# FPGA_03.net
KiCad netlist of a schematic drawn in Altium Designer
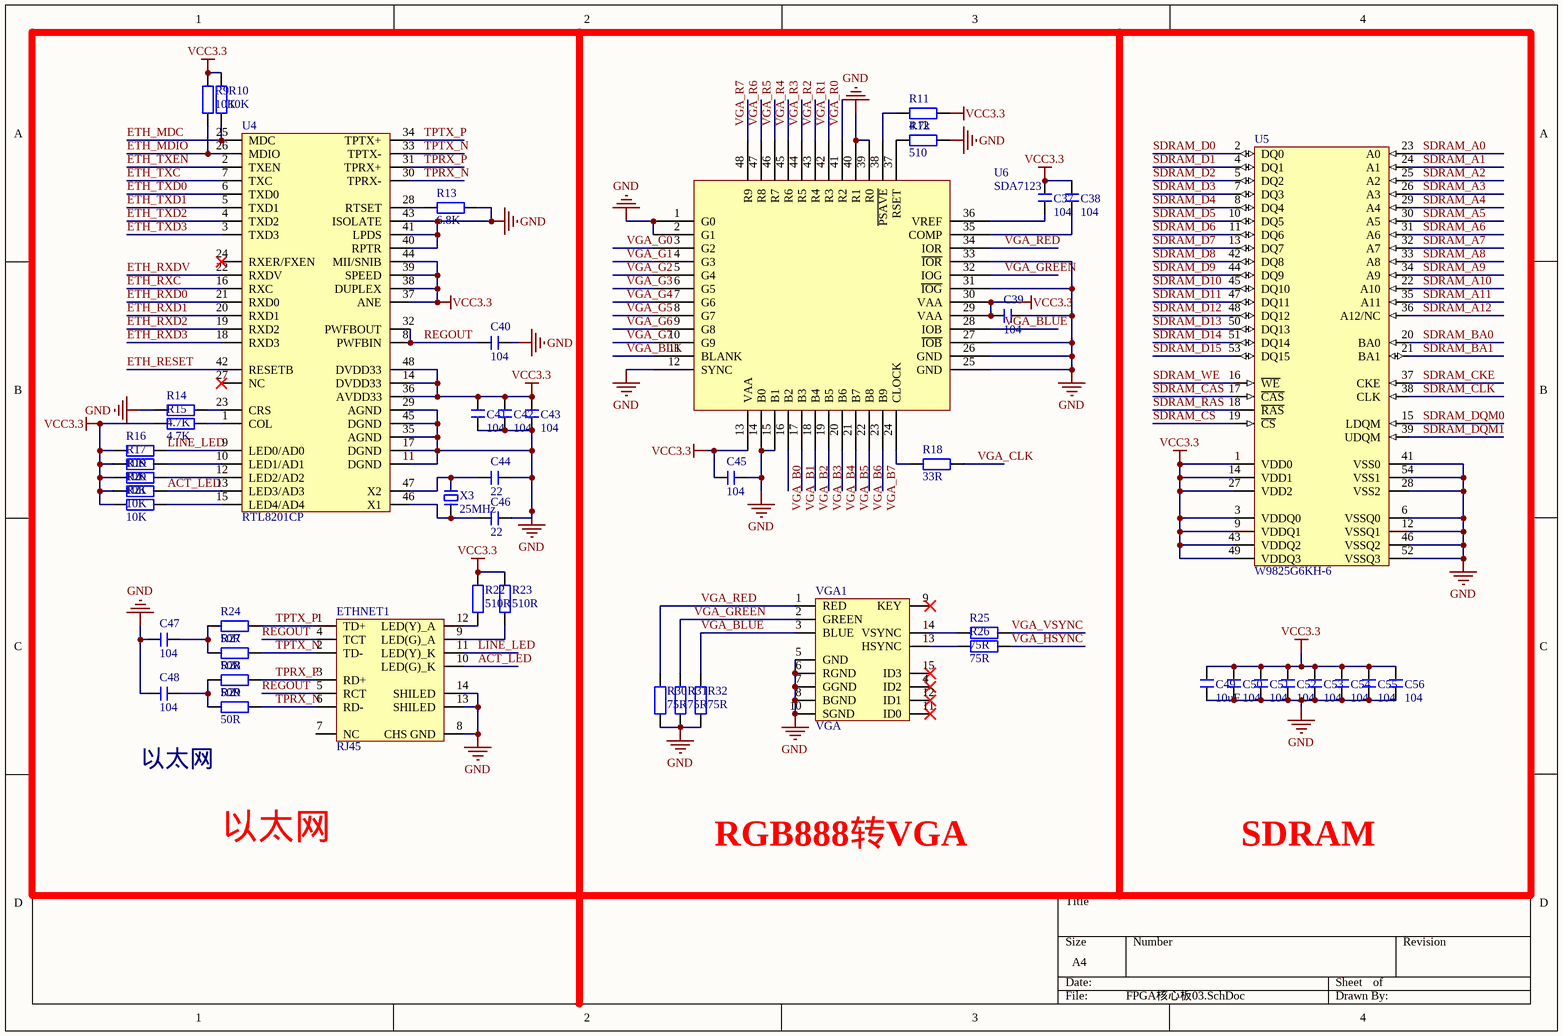
[diagram p0: FPGA核心板03.SchDoc]

(export (version "E")
  (design (tool "Eeschema 10.0.6"))
  (components
    (comp (ref "C37")
      (value "104")
      (footprint "C 0603_L")
      (description "贴片电容")
      (libsource (lib "0.1 - 电阻-电容-电感") (part "C"))
    )
    (comp (ref "C38")
      (value "104")
      (footprint "C 0603_L")
      (description "贴片电容")
      (libsource (lib "0.1 - 电阻-电容-电感") (part "C"))
    )
    (comp (ref "C39")
      (value "104")
      (footprint "C 0603_L")
      (description "贴片电容")
      (libsource (lib "0.1 - 电阻-电容-电感") (part "C"))
    )
    (comp (ref "C40")
      (value "104")
      (footprint "C 0603_L")
      (description "贴片电容")
      (libsource (lib "0.1 - 电阻-电容-电感") (part "C"))
    )
    (comp (ref "C41")
      (value "104")
      (footprint "C 0603_L")
      (description "贴片电容")
      (libsource (lib "0.1 - 电阻-电容-电感") (part "C"))
    )
    (comp (ref "C42")
      (value "104")
      (footprint "C 0603_L")
      (description "贴片电容")
      (libsource (lib "0.1 - 电阻-电容-电感") (part "C"))
    )
    (comp (ref "C43")
      (value "104")
      (footprint "C 0603_L")
      (description "贴片电容")
      (libsource (lib "0.1 - 电阻-电容-电感") (part "C"))
    )
    (comp (ref "C44")
      (value "22")
      (footprint "C 0603_L")
      (description "贴片电容")
      (libsource (lib "0.1 - 电阻-电容-电感") (part "C"))
    )
    (comp (ref "C45")
      (value "104")
      (footprint "C 0603_L")
      (description "贴片电容")
      (libsource (lib "0.1 - 电阻-电容-电感") (part "C"))
    )
    (comp (ref "C46")
      (value "22")
      (footprint "C 0603_L")
      (description "贴片电容")
      (libsource (lib "0.1 - 电阻-电容-电感") (part "C"))
    )
    (comp (ref "C47")
      (value "104")
      (footprint "C 0603_L")
      (description "贴片电容")
      (libsource (lib "0.1 - 电阻-电容-电感") (part "C"))
    )
    (comp (ref "C48")
      (value "104")
      (footprint "C 0603_L")
      (description "贴片电容")
      (libsource (lib "0.1 - 电阻-电容-电感") (part "C"))
    )
    (comp (ref "C49")
      (value "10uF")
      (footprint "C 0603_L")
      (description "贴片电容")
      (libsource (lib "0.1 - 电阻-电容-电感") (part "C"))
    )
    (comp (ref "C50")
      (value "104")
      (footprint "C 0603_L")
      (description "贴片电容")
      (libsource (lib "0.1 - 电阻-电容-电感") (part "C"))
    )
    (comp (ref "C51")
      (value "104")
      (footprint "C 0603_L")
      (description "贴片电容")
      (libsource (lib "0.1 - 电阻-电容-电感") (part "C"))
    )
    (comp (ref "C52")
      (value "104")
      (footprint "C 0603_L")
      (description "贴片电容")
      (libsource (lib "0.1 - 电阻-电容-电感") (part "C"))
    )
    (comp (ref "C53")
      (value "104")
      (footprint "C 0603_L")
      (description "贴片电容")
      (libsource (lib "0.1 - 电阻-电容-电感") (part "C"))
    )
    (comp (ref "C54")
      (value "104")
      (footprint "C 0603_L")
      (description "贴片电容")
      (libsource (lib "0.1 - 电阻-电容-电感") (part "C"))
    )
    (comp (ref "C55")
      (value "104")
      (footprint "C 0603_L")
      (description "贴片电容")
      (libsource (lib "0.1 - 电阻-电容-电感") (part "C"))
    )
    (comp (ref "C56")
      (value "104")
      (footprint "C 0603_L")
      (description "贴片电容")
      (libsource (lib "0.1 - 电阻-电容-电感") (part "C"))
    )
    (comp (ref "ETHNET1") (value "RJ45") (footprint "RJ-45A12") (libsource (lib "PIONEER") (part "HR911105")))
    (comp (ref "R9")
      (value "10K")
      (footprint "R 0603_L")
      (description "贴片电阻")
      (fields (field (name "版权归属") "来自淘宝 ID：黄晶宝石"))
      (libsource (lib "0.1 - 电阻-电容-电感") (part "R"))
    )
    (comp (ref "R10")
      (value "10K")
      (footprint "R 0603_L")
      (description "贴片电阻")
      (fields (field (name "版权归属") "来自淘宝 ID：黄晶宝石"))
      (libsource (lib "0.1 - 电阻-电容-电感") (part "R"))
    )
    (comp (ref "R11")
      (value "4.7k")
      (footprint "R 0603_L")
      (description "贴片电阻")
      (fields (field (name "版权归属") "来自淘宝 ID：黄晶宝石"))
      (libsource (lib "0.1 - 电阻-电容-电感") (part "R"))
    )
    (comp (ref "R12")
      (value "510")
      (footprint "R 0603_L")
      (description "贴片电阻")
      (fields (field (name "版权归属") "来自淘宝 ID：黄晶宝石"))
      (libsource (lib "0.1 - 电阻-电容-电感") (part "R"))
    )
    (comp (ref "R13")
      (value "6.8K")
      (footprint "R 0603_L")
      (description "贴片电阻")
      (fields (field (name "版权归属") "来自淘宝 ID：黄晶宝石"))
      (libsource (lib "0.1 - 电阻-电容-电感") (part "R"))
    )
    (comp (ref "R14")
      (value "4.7K")
      (footprint "R 0603_L")
      (description "贴片电阻")
      (fields (field (name "版权归属") "来自淘宝 ID：黄晶宝石"))
      (libsource (lib "0.1 - 电阻-电容-电感") (part "R"))
    )
    (comp (ref "R15")
      (value "4.7K")
      (footprint "R 0603_L")
      (description "贴片电阻")
      (fields (field (name "版权归属") "来自淘宝 ID：黄晶宝石"))
      (libsource (lib "0.1 - 电阻-电容-电感") (part "R"))
    )
    (comp (ref "R16")
      (value "10K")
      (footprint "R 0603_L")
      (description "贴片电阻")
      (fields (field (name "版权归属") "来自淘宝 ID：黄晶宝石"))
      (libsource (lib "0.1 - 电阻-电容-电感") (part "R"))
    )
    (comp (ref "R17")
      (value "10K")
      (footprint "R 0603_L")
      (description "贴片电阻")
      (fields (field (name "版权归属") "来自淘宝 ID：黄晶宝石"))
      (libsource (lib "0.1 - 电阻-电容-电感") (part "R"))
    )
    (comp (ref "R18")
      (value "33R")
      (footprint "R 0603_L")
      (description "贴片电阻")
      (fields (field (name "版权归属") "来自淘宝 ID：黄晶宝石"))
      (libsource (lib "0.1 - 电阻-电容-电感") (part "R"))
    )
    (comp (ref "R19")
      (value "10K")
      (footprint "R 0603_L")
      (description "贴片电阻")
      (fields (field (name "版权归属") "来自淘宝 ID：黄晶宝石"))
      (libsource (lib "0.1 - 电阻-电容-电感") (part "R"))
    )
    (comp (ref "R20")
      (value "10K")
      (footprint "R 0603_L")
      (description "贴片电阻")
      (fields (field (name "版权归属") "来自淘宝 ID：黄晶宝石"))
      (libsource (lib "0.1 - 电阻-电容-电感") (part "R"))
    )
    (comp (ref "R21")
      (value "10K")
      (footprint "R 0603_L")
      (description "贴片电阻")
      (fields (field (name "版权归属") "来自淘宝 ID：黄晶宝石"))
      (libsource (lib "0.1 - 电阻-电容-电感") (part "R"))
    )
    (comp (ref "R22")
      (value "510R")
      (footprint "R 0603_L")
      (description "贴片电阻")
      (fields (field (name "版权归属") "来自淘宝 ID：黄晶宝石"))
      (libsource (lib "0.1 - 电阻-电容-电感") (part "R"))
    )
    (comp (ref "R23")
      (value "510R")
      (footprint "R 0603_L")
      (description "贴片电阻")
      (fields (field (name "版权归属") "来自淘宝 ID：黄晶宝石"))
      (libsource (lib "0.1 - 电阻-电容-电感") (part "R"))
    )
    (comp (ref "R24")
      (value "50R")
      (footprint "R 0603_L")
      (description "贴片电阻")
      (fields (field (name "版权归属") "来自淘宝 ID：黄晶宝石"))
      (libsource (lib "0.1 - 电阻-电容-电感") (part "R"))
    )
    (comp (ref "R25")
      (value "75R")
      (footprint "R 0603_L")
      (description "贴片电阻")
      (fields (field (name "版权归属") "来自淘宝 ID：黄晶宝石"))
      (libsource (lib "0.1 - 电阻-电容-电感") (part "R"))
    )
    (comp (ref "R26")
      (value "75R")
      (footprint "R 0603_L")
      (description "贴片电阻")
      (fields (field (name "版权归属") "来自淘宝 ID：黄晶宝石"))
      (libsource (lib "0.1 - 电阻-电容-电感") (part "R"))
    )
    (comp (ref "R27")
      (value "50R")
      (footprint "R 0603_L")
      (description "贴片电阻")
      (fields (field (name "版权归属") "来自淘宝 ID：黄晶宝石"))
      (libsource (lib "0.1 - 电阻-电容-电感") (part "R"))
    )
    (comp (ref "R28")
      (value "50R")
      (footprint "R 0603_L")
      (description "贴片电阻")
      (fields (field (name "版权归属") "来自淘宝 ID：黄晶宝石"))
      (libsource (lib "0.1 - 电阻-电容-电感") (part "R"))
    )
    (comp (ref "R29")
      (value "50R")
      (footprint "R 0603_L")
      (description "贴片电阻")
      (fields (field (name "版权归属") "来自淘宝 ID：黄晶宝石"))
      (libsource (lib "0.1 - 电阻-电容-电感") (part "R"))
    )
    (comp (ref "R30")
      (value "75R")
      (footprint "R 0603_L")
      (description "贴片电阻")
      (fields (field (name "版权归属") "来自淘宝 ID：黄晶宝石"))
      (libsource (lib "0.1 - 电阻-电容-电感") (part "R"))
    )
    (comp (ref "R31")
      (value "75R")
      (footprint "R 0603_L")
      (description "贴片电阻")
      (fields (field (name "版权归属") "来自淘宝 ID：黄晶宝石"))
      (libsource (lib "0.1 - 电阻-电容-电感") (part "R"))
    )
    (comp (ref "R32")
      (value "75R")
      (footprint "R 0603_L")
      (description "贴片电阻")
      (fields (field (name "版权归属") "来自淘宝 ID：黄晶宝石"))
      (libsource (lib "0.1 - 电阻-电容-电感") (part "R"))
    )
    (comp (ref "U4")
      (value "RTL8201CP")
      (footprint "LQFP48 7X7_L")
      (description "ETH PHY")
      (libsource (lib "PIONEER") (part "RTL8201CP"))
    )
    (comp (ref "U5")
      (value "W9825G6KH-6")
      (footprint "TSOP54")
      (description "32MB SDRAM")
      (libsource (lib "PIONEER") (part "IS42S16160B"))
    )
    (comp (ref "U6")
      (value "SDA7123")
      (footprint "LQFP48 7X7_N")
      (libsource (lib "Schlib1") (part "SDA7123"))
    )
    (comp (ref "VGA1") (value "VGA") (footprint "VGA15B") (libsource (lib "PIONEER") (part "VGA")))
    (comp (ref "X3")
      (value "25MHz")
      (footprint "OSC HC-49S")
      (description "2脚无源脚晶振")
      (fields (field (name "版权归属") "源创客"))
      (libsource (lib "2.0 - 保险丝-晶振-光耦") (part "XTAL-2P"))
    )
  )
  (nets
    (net (code "1") (name "/ACT_LED") (class "Default")
      (node (ref "ETHNET1") (pin "10") (pinfunction "LED(G)_K_10") (pintype "passive"))
      (node (ref "R20") (pin "2") (pinfunction "2_2") (pintype "passive"))
      (node (ref "U4") (pin "13") (pinfunction "LED3/AD3_13") (pintype "passive"))
    )
    (net (code "2") (name "/ETH_MDC") (class "Default")
      (node (ref "R10") (pin "1") (pinfunction "1_1") (pintype "passive"))
      (node (ref "U4") (pin "25") (pinfunction "MDC_25") (pintype "passive"))
    )
    (net (code "3") (name "/ETH_MDIO") (class "Default")
      (node (ref "R9") (pin "1") (pinfunction "1_1") (pintype "passive"))
      (node (ref "U4") (pin "26") (pinfunction "MDIO_26") (pintype "passive"))
    )
    (net (code "4") (name "/ETH_RESET") (class "Default")
      (node (ref "U4") (pin "42") (pinfunction "RESETB_42") (pintype "passive"))
    )
    (net (code "5") (name "/ETH_RXC") (class "Default")
      (node (ref "U4") (pin "16") (pinfunction "RXC_16") (pintype "passive"))
    )
    (net (code "6") (name "/ETH_RXD0") (class "Default")
      (node (ref "U4") (pin "21") (pinfunction "RXD0_21") (pintype "passive"))
    )
    (net (code "7") (name "/ETH_RXD1") (class "Default")
      (node (ref "U4") (pin "20") (pinfunction "RXD1_20") (pintype "passive"))
    )
    (net (code "8") (name "/ETH_RXD2") (class "Default")
      (node (ref "U4") (pin "19") (pinfunction "RXD2_19") (pintype "passive"))
    )
    (net (code "9") (name "/ETH_RXD3") (class "Default")
      (node (ref "U4") (pin "18") (pinfunction "RXD3_18") (pintype "passive"))
    )
    (net (code "10") (name "/ETH_RXDV") (class "Default")
      (node (ref "U4") (pin "22") (pinfunction "RXDV_22") (pintype "passive"))
    )
    (net (code "11") (name "/ETH_TXC") (class "Default")
      (node (ref "U4") (pin "7") (pinfunction "TXC_7") (pintype "passive"))
    )
    (net (code "12") (name "/ETH_TXD0") (class "Default")
      (node (ref "U4") (pin "6") (pinfunction "TXD0_6") (pintype "passive"))
    )
    (net (code "13") (name "/ETH_TXD1") (class "Default")
      (node (ref "U4") (pin "5") (pinfunction "TXD1_5") (pintype "passive"))
    )
    (net (code "14") (name "/ETH_TXD2") (class "Default")
      (node (ref "U4") (pin "4") (pinfunction "TXD2_4") (pintype "passive"))
    )
    (net (code "15") (name "/ETH_TXD3") (class "Default")
      (node (ref "U4") (pin "3") (pinfunction "TXD3_3") (pintype "passive"))
    )
    (net (code "16") (name "/ETH_TXEN") (class "Default")
      (node (ref "U4") (pin "2") (pinfunction "TXEN_2") (pintype "passive"))
    )
    (net (code "17") (name "/LINE_LED") (class "Default")
      (node (ref "ETHNET1") (pin "11") (pinfunction "LED(Y)_K_11") (pintype "passive"))
      (node (ref "R16") (pin "2") (pinfunction "2_2") (pintype "passive"))
      (node (ref "U4") (pin "9") (pinfunction "LED0/AD0_9") (pintype "passive"))
    )
    (net (code "18") (name "/REGOUT") (class "Default")
      (node (ref "C40") (pin "2") (pinfunction "2_2") (pintype "passive"))
      (node (ref "ETHNET1") (pin "4") (pinfunction "TCT_4") (pintype "passive"))
      (node (ref "ETHNET1") (pin "5") (pinfunction "RCT_5") (pintype "passive"))
      (node (ref "U4") (pin "32") (pinfunction "PWFBOUT_32") (pintype "passive"))
      (node (ref "U4") (pin "8") (pinfunction "PWFBIN_8") (pintype "passive"))
    )
    (net (code "19") (name "/SDRAM_A0") (class "Default")
      (node (ref "U5") (pin "23") (pinfunction "A0_23") (pintype "input"))
    )
    (net (code "20") (name "/SDRAM_A1") (class "Default")
      (node (ref "U5") (pin "24") (pinfunction "A1_24") (pintype "input"))
    )
    (net (code "21") (name "/SDRAM_A2") (class "Default")
      (node (ref "U5") (pin "25") (pinfunction "A2_25") (pintype "input"))
    )
    (net (code "22") (name "/SDRAM_A3") (class "Default")
      (node (ref "U5") (pin "26") (pinfunction "A3_26") (pintype "input"))
    )
    (net (code "23") (name "/SDRAM_A4") (class "Default")
      (node (ref "U5") (pin "29") (pinfunction "A4_29") (pintype "input"))
    )
    (net (code "24") (name "/SDRAM_A5") (class "Default")
      (node (ref "U5") (pin "30") (pinfunction "A5_30") (pintype "input"))
    )
    (net (code "25") (name "/SDRAM_A6") (class "Default")
      (node (ref "U5") (pin "31") (pinfunction "A6_31") (pintype "input"))
    )
    (net (code "26") (name "/SDRAM_A7") (class "Default")
      (node (ref "U5") (pin "32") (pinfunction "A7_32") (pintype "input"))
    )
    (net (code "27") (name "/SDRAM_A8") (class "Default")
      (node (ref "U5") (pin "33") (pinfunction "A8_33") (pintype "input"))
    )
    (net (code "28") (name "/SDRAM_A9") (class "Default")
      (node (ref "U5") (pin "34") (pinfunction "A9_34") (pintype "input"))
    )
    (net (code "29") (name "/SDRAM_A10") (class "Default")
      (node (ref "U5") (pin "22") (pinfunction "A10_22") (pintype "input"))
    )
    (net (code "30") (name "/SDRAM_A11") (class "Default")
      (node (ref "U5") (pin "35") (pinfunction "A11_35") (pintype "input"))
    )
    (net (code "31") (name "/SDRAM_A12") (class "Default")
      (node (ref "U5") (pin "36") (pinfunction "A12/NC_36") (pintype "input"))
    )
    (net (code "32") (name "/SDRAM_BA0") (class "Default")
      (node (ref "U5") (pin "20") (pinfunction "BA0_20") (pintype "input"))
    )
    (net (code "33") (name "/SDRAM_BA1") (class "Default")
      (node (ref "U5") (pin "21") (pinfunction "BA1_21") (pintype "bidirectional"))
    )
    (net (code "34") (name "/SDRAM_CAS") (class "Default")
      (node (ref "U5") (pin "17") (pinfunction "~{CAS}_17") (pintype "input"))
    )
    (net (code "35") (name "/SDRAM_CKE") (class "Default")
      (node (ref "U5") (pin "37") (pinfunction "CKE_37") (pintype "input"))
    )
    (net (code "36") (name "/SDRAM_CLK") (class "Default")
      (node (ref "U5") (pin "38") (pinfunction "CLK_38") (pintype "input"))
    )
    (net (code "37") (name "/SDRAM_CS") (class "Default")
      (node (ref "U5") (pin "19") (pinfunction "~{CS}_19") (pintype "input"))
    )
    (net (code "38") (name "/SDRAM_D0") (class "Default")
      (node (ref "U5") (pin "2") (pinfunction "DQ0_2") (pintype "bidirectional"))
    )
    (net (code "39") (name "/SDRAM_D1") (class "Default")
      (node (ref "U5") (pin "4") (pinfunction "DQ1_4") (pintype "bidirectional"))
    )
    (net (code "40") (name "/SDRAM_D2") (class "Default")
      (node (ref "U5") (pin "5") (pinfunction "DQ2_5") (pintype "bidirectional"))
    )
    (net (code "41") (name "/SDRAM_D3") (class "Default")
      (node (ref "U5") (pin "7") (pinfunction "DQ3_7") (pintype "bidirectional"))
    )
    (net (code "42") (name "/SDRAM_D4") (class "Default")
      (node (ref "U5") (pin "8") (pinfunction "DQ4_8") (pintype "bidirectional"))
    )
    (net (code "43") (name "/SDRAM_D5") (class "Default")
      (node (ref "U5") (pin "10") (pinfunction "DQ5_10") (pintype "bidirectional"))
    )
    (net (code "44") (name "/SDRAM_D6") (class "Default")
      (node (ref "U5") (pin "11") (pinfunction "DQ6_11") (pintype "bidirectional"))
    )
    (net (code "45") (name "/SDRAM_D7") (class "Default")
      (node (ref "U5") (pin "13") (pinfunction "DQ7_13") (pintype "bidirectional"))
    )
    (net (code "46") (name "/SDRAM_D8") (class "Default")
      (node (ref "U5") (pin "42") (pinfunction "DQ8_42") (pintype "bidirectional"))
    )
    (net (code "47") (name "/SDRAM_D9") (class "Default")
      (node (ref "U5") (pin "44") (pinfunction "DQ9_44") (pintype "bidirectional"))
    )
    (net (code "48") (name "/SDRAM_D10") (class "Default")
      (node (ref "U5") (pin "45") (pinfunction "DQ10_45") (pintype "bidirectional"))
    )
    (net (code "49") (name "/SDRAM_D11") (class "Default")
      (node (ref "U5") (pin "47") (pinfunction "DQ11_47") (pintype "bidirectional"))
    )
    (net (code "50") (name "/SDRAM_D12") (class "Default")
      (node (ref "U5") (pin "48") (pinfunction "DQ12_48") (pintype "bidirectional"))
    )
    (net (code "51") (name "/SDRAM_D13") (class "Default")
      (node (ref "U5") (pin "50") (pinfunction "DQ13_50") (pintype "bidirectional"))
    )
    (net (code "52") (name "/SDRAM_D14") (class "Default")
      (node (ref "U5") (pin "51") (pinfunction "DQ14_51") (pintype "bidirectional"))
    )
    (net (code "53") (name "/SDRAM_D15") (class "Default")
      (node (ref "U5") (pin "53") (pinfunction "DQ15_53") (pintype "bidirectional"))
    )
    (net (code "54") (name "/SDRAM_DQM0") (class "Default")
      (node (ref "U5") (pin "15") (pinfunction "LDQM_15") (pintype "input"))
    )
    (net (code "55") (name "/SDRAM_DQM1") (class "Default")
      (node (ref "U5") (pin "39") (pinfunction "UDQM_39") (pintype "input"))
    )
    (net (code "56") (name "/SDRAM_RAS") (class "Default")
      (node (ref "U5") (pin "18") (pinfunction "~{RAS}_18") (pintype "passive"))
    )
    (net (code "57") (name "/SDRAM_WE") (class "Default")
      (node (ref "U5") (pin "16") (pinfunction "~{WE}_16") (pintype "input"))
    )
    (net (code "58") (name "/TPRX_N") (class "Default")
      (node (ref "ETHNET1") (pin "6") (pinfunction "RD-_6") (pintype "passive"))
      (node (ref "R29") (pin "2") (pinfunction "2_2") (pintype "passive"))
      (node (ref "U4") (pin "30") (pinfunction "TPRX-_30") (pintype "passive"))
    )
    (net (code "59") (name "/TPRX_P") (class "Default")
      (node (ref "ETHNET1") (pin "3") (pinfunction "RD+_3") (pintype "passive"))
      (node (ref "R28") (pin "2") (pinfunction "2_2") (pintype "passive"))
      (node (ref "U4") (pin "31") (pinfunction "TPRX+_31") (pintype "passive"))
    )
    (net (code "60") (name "/TPTX_N") (class "Default")
      (node (ref "ETHNET1") (pin "2") (pinfunction "TD-_2") (pintype "passive"))
      (node (ref "R27") (pin "2") (pinfunction "2_2") (pintype "passive"))
      (node (ref "U4") (pin "33") (pinfunction "TPTX-_33") (pintype "passive"))
    )
    (net (code "61") (name "/TPTX_P") (class "Default")
      (node (ref "ETHNET1") (pin "1") (pinfunction "TD+_1") (pintype "passive"))
      (node (ref "R24") (pin "2") (pinfunction "2_2") (pintype "passive"))
      (node (ref "U4") (pin "34") (pinfunction "TPTX+_34") (pintype "passive"))
    )
    (net (code "62") (name "/VGA_B0") (class "Default")
      (node (ref "U6") (pin "16") (pinfunction "B2_16") (pintype "passive"))
    )
    (net (code "63") (name "/VGA_B1") (class "Default")
      (node (ref "U6") (pin "17") (pinfunction "B3_17") (pintype "passive"))
    )
    (net (code "64") (name "/VGA_B2") (class "Default")
      (node (ref "U6") (pin "18") (pinfunction "B4_18") (pintype "passive"))
    )
    (net (code "65") (name "/VGA_B3") (class "Default")
      (node (ref "U6") (pin "19") (pinfunction "B5_19") (pintype "passive"))
    )
    (net (code "66") (name "/VGA_B4") (class "Default")
      (node (ref "U6") (pin "20") (pinfunction "B6_20") (pintype "passive"))
    )
    (net (code "67") (name "/VGA_B5") (class "Default")
      (node (ref "U6") (pin "21") (pinfunction "B7_21") (pintype "passive"))
    )
    (net (code "68") (name "/VGA_B6") (class "Default")
      (node (ref "U6") (pin "22") (pinfunction "B8_22") (pintype "passive"))
    )
    (net (code "69") (name "/VGA_B7") (class "Default")
      (node (ref "U6") (pin "23") (pinfunction "B9_23") (pintype "passive"))
    )
    (net (code "70") (name "/VGA_BLK") (class "Default")
      (node (ref "U6") (pin "11") (pinfunction "BLANK_11") (pintype "passive"))
    )
    (net (code "71") (name "/VGA_BLUE") (class "Default")
      (node (ref "R32") (pin "2") (pinfunction "2_2") (pintype "passive"))
      (node (ref "U6") (pin "28") (pinfunction "IOB_28") (pintype "passive"))
      (node (ref "VGA1") (pin "3") (pinfunction "BLUE_3") (pintype "passive"))
    )
    (net (code "72") (name "/VGA_CLK") (class "Default")
      (node (ref "R18") (pin "2") (pinfunction "2_2") (pintype "passive"))
    )
    (net (code "73") (name "/VGA_G0") (class "Default")
      (node (ref "U6") (pin "3") (pinfunction "G2_3") (pintype "passive"))
    )
    (net (code "74") (name "/VGA_G1") (class "Default")
      (node (ref "U6") (pin "4") (pinfunction "G3_4") (pintype "passive"))
    )
    (net (code "75") (name "/VGA_G2") (class "Default")
      (node (ref "U6") (pin "5") (pinfunction "G4_5") (pintype "passive"))
    )
    (net (code "76") (name "/VGA_G3") (class "Default")
      (node (ref "U6") (pin "6") (pinfunction "G5_6") (pintype "passive"))
    )
    (net (code "77") (name "/VGA_G4") (class "Default")
      (node (ref "U6") (pin "7") (pinfunction "G6_7") (pintype "passive"))
    )
    (net (code "78") (name "/VGA_G5") (class "Default")
      (node (ref "U6") (pin "8") (pinfunction "G7_8") (pintype "passive"))
    )
    (net (code "79") (name "/VGA_G6") (class "Default")
      (node (ref "U6") (pin "9") (pinfunction "G8_9") (pintype "passive"))
    )
    (net (code "80") (name "/VGA_G7") (class "Default")
      (node (ref "U6") (pin "10") (pinfunction "G9_10") (pintype "passive"))
    )
    (net (code "81") (name "/VGA_GREEN") (class "Default")
      (node (ref "R31") (pin "2") (pinfunction "2_2") (pintype "passive"))
      (node (ref "U6") (pin "32") (pinfunction "IOG_32") (pintype "passive"))
      (node (ref "VGA1") (pin "2") (pinfunction "GREEN_2") (pintype "passive"))
    )
    (net (code "82") (name "/VGA_HSYNC") (class "Default")
      (node (ref "R26") (pin "1") (pinfunction "1_1") (pintype "passive"))
    )
    (net (code "83") (name "/VGA_R0") (class "Default")
      (node (ref "U6") (pin "41") (pinfunction "R2_41") (pintype "passive"))
    )
    (net (code "84") (name "/VGA_R1") (class "Default")
      (node (ref "U6") (pin "42") (pinfunction "R3_42") (pintype "passive"))
    )
    (net (code "85") (name "/VGA_R2") (class "Default")
      (node (ref "U6") (pin "43") (pinfunction "R4_43") (pintype "passive"))
    )
    (net (code "86") (name "/VGA_R3") (class "Default")
      (node (ref "U6") (pin "44") (pinfunction "R5_44") (pintype "passive"))
    )
    (net (code "87") (name "/VGA_R4") (class "Default")
      (node (ref "U6") (pin "45") (pinfunction "R6_45") (pintype "passive"))
    )
    (net (code "88") (name "/VGA_R5") (class "Default")
      (node (ref "U6") (pin "46") (pinfunction "R7_46") (pintype "passive"))
    )
    (net (code "89") (name "/VGA_R6") (class "Default")
      (node (ref "U6") (pin "47") (pinfunction "R8_47") (pintype "passive"))
    )
    (net (code "90") (name "/VGA_R7") (class "Default")
      (node (ref "U6") (pin "48") (pinfunction "R9_48") (pintype "passive"))
    )
    (net (code "91") (name "/VGA_RED") (class "Default")
      (node (ref "R30") (pin "2") (pinfunction "2_2") (pintype "passive"))
      (node (ref "U6") (pin "34") (pinfunction "IOR_34") (pintype "passive"))
      (node (ref "VGA1") (pin "1") (pinfunction "RED_1") (pintype "passive"))
    )
    (net (code "92") (name "/VGA_VSYNC") (class "Default")
      (node (ref "R25") (pin "1") (pinfunction "1_1") (pintype "passive"))
    )
    (net (code "93") (name "GND") (class "Default")
      (node (ref "C39") (pin "1") (pinfunction "1_1") (pintype "passive"))
      (node (ref "C40") (pin "1") (pinfunction "1_1") (pintype "passive"))
      (node (ref "C41") (pin "1") (pinfunction "1_1") (pintype "passive"))
      (node (ref "C42") (pin "1") (pinfunction "1_1") (pintype "passive"))
      (node (ref "C43") (pin "1") (pinfunction "1_1") (pintype "passive"))
      (node (ref "C44") (pin "2") (pinfunction "2_2") (pintype "passive"))
      (node (ref "C45") (pin "2") (pinfunction "2_2") (pintype "passive"))
      (node (ref "C46") (pin "2") (pinfunction "2_2") (pintype "passive"))
      (node (ref "C47") (pin "2") (pinfunction "2_2") (pintype "passive"))
      (node (ref "C48") (pin "2") (pinfunction "2_2") (pintype "passive"))
      (node (ref "C49") (pin "1") (pinfunction "1_1") (pintype "passive"))
      (node (ref "C50") (pin "1") (pinfunction "1_1") (pintype "passive"))
      (node (ref "C51") (pin "1") (pinfunction "1_1") (pintype "passive"))
      (node (ref "C52") (pin "1") (pinfunction "1_1") (pintype "passive"))
      (node (ref "C53") (pin "1") (pinfunction "1_1") (pintype "passive"))
      (node (ref "C54") (pin "1") (pinfunction "1_1") (pintype "passive"))
      (node (ref "C55") (pin "1") (pinfunction "1_1") (pintype "passive"))
      (node (ref "C56") (pin "1") (pinfunction "1_1") (pintype "passive"))
      (node (ref "ETHNET1") (pin "13") (pinfunction "SHILED_13") (pintype "passive"))
      (node (ref "ETHNET1") (pin "14") (pinfunction "SHILED_14") (pintype "passive"))
      (node (ref "ETHNET1") (pin "8") (pinfunction "CHS_GND_8") (pintype "passive"))
      (node (ref "R12") (pin "2") (pinfunction "2_2") (pintype "passive"))
      (node (ref "R13") (pin "2") (pinfunction "2_2") (pintype "passive"))
      (node (ref "R14") (pin "1") (pinfunction "1_1") (pintype "passive"))
      (node (ref "R30") (pin "1") (pinfunction "1_1") (pintype "passive"))
      (node (ref "R31") (pin "1") (pinfunction "1_1") (pintype "passive"))
      (node (ref "R32") (pin "1") (pinfunction "1_1") (pintype "passive"))
      (node (ref "U4") (pin "11") (pinfunction "DGND_11") (pintype "passive"))
      (node (ref "U4") (pin "17") (pinfunction "DGND_17") (pintype "passive"))
      (node (ref "U4") (pin "29") (pinfunction "AGND_29") (pintype "passive"))
      (node (ref "U4") (pin "35") (pinfunction "AGND_35") (pintype "passive"))
      (node (ref "U4") (pin "40") (pinfunction "RPTR_40") (pintype "passive"))
      (node (ref "U4") (pin "41") (pinfunction "LPDS_41") (pintype "passive"))
      (node (ref "U4") (pin "43") (pinfunction "ISOLATE_43") (pintype "passive"))
      (node (ref "U4") (pin "45") (pinfunction "DGND_45") (pintype "passive"))
      (node (ref "U5") (pin "12") (pinfunction "VSSQ1_12") (pintype "power_in"))
      (node (ref "U5") (pin "28") (pinfunction "VSS2_28") (pintype "power_in"))
      (node (ref "U5") (pin "41") (pinfunction "VSS0_41") (pintype "power_in"))
      (node (ref "U5") (pin "46") (pinfunction "VSSQ2_46") (pintype "power_in"))
      (node (ref "U5") (pin "52") (pinfunction "VSSQ3_52") (pintype "power_in"))
      (node (ref "U5") (pin "54") (pinfunction "VSS1_54") (pintype "power_in"))
      (node (ref "U5") (pin "6") (pinfunction "VSSQ0_6") (pintype "power_in"))
      (node (ref "U6") (pin "1") (pinfunction "G0_1") (pintype "passive"))
      (node (ref "U6") (pin "12") (pinfunction "SYNC_12") (pintype "passive"))
      (node (ref "U6") (pin "14") (pinfunction "B0_14") (pintype "passive"))
      (node (ref "U6") (pin "15") (pinfunction "B1_15") (pintype "passive"))
      (node (ref "U6") (pin "2") (pinfunction "G1_2") (pintype "passive"))
      (node (ref "U6") (pin "25") (pinfunction "GND_25") (pintype "passive"))
      (node (ref "U6") (pin "26") (pinfunction "GND_26") (pintype "passive"))
      (node (ref "U6") (pin "27") (pinfunction "~{IOB}_27") (pintype "passive"))
      (node (ref "U6") (pin "31") (pinfunction "~{IOG}_31") (pintype "passive"))
      (node (ref "U6") (pin "33") (pinfunction "~{IOR}_33") (pintype "passive"))
      (node (ref "U6") (pin "39") (pinfunction "R0_39") (pintype "passive"))
      (node (ref "U6") (pin "40") (pinfunction "R1_40") (pintype "passive"))
      (node (ref "VGA1") (pin "10") (pinfunction "SGND_10") (pintype "passive"))
      (node (ref "VGA1") (pin "5") (pinfunction "GND_5") (pintype "passive"))
      (node (ref "VGA1") (pin "6") (pinfunction "RGND_6") (pintype "passive"))
      (node (ref "VGA1") (pin "7") (pinfunction "GGND_7") (pintype "passive"))
      (node (ref "VGA1") (pin "8") (pinfunction "BGND_8") (pintype "passive"))
    )
    (net (code "94") (name "Net-(C47-Pad1)") (class "Default")
      (node (ref "C47") (pin "1") (pinfunction "1_1") (pintype "passive"))
      (node (ref "R24") (pin "1") (pinfunction "1_1") (pintype "passive"))
      (node (ref "R27") (pin "1") (pinfunction "1_1") (pintype "passive"))
    )
    (net (code "95") (name "Net-(C48-Pad1)") (class "Default")
      (node (ref "C48") (pin "1") (pinfunction "1_1") (pintype "passive"))
      (node (ref "R28") (pin "1") (pinfunction "1_1") (pintype "passive"))
      (node (ref "R29") (pin "1") (pinfunction "1_1") (pintype "passive"))
    )
    (net (code "96") (name "Net-(ETHNET1-LED(G)_A)") (class "Default")
      (node (ref "ETHNET1") (pin "9") (pinfunction "LED(G)_A_9") (pintype "passive"))
      (node (ref "R23") (pin "1") (pinfunction "1_1") (pintype "passive"))
    )
    (net (code "97") (name "Net-(ETHNET1-LED(Y)_A)") (class "Default")
      (node (ref "ETHNET1") (pin "12") (pinfunction "LED(Y)_A_12") (pintype "passive"))
      (node (ref "R22") (pin "1") (pinfunction "1_1") (pintype "passive"))
    )
    (net (code "98") (name "Net-(U4-COL)") (class "Default")
      (node (ref "R15") (pin "2") (pinfunction "2_2") (pintype "passive"))
      (node (ref "U4") (pin "1") (pinfunction "COL_1") (pintype "passive"))
    )
    (net (code "99") (name "Net-(U4-CRS)") (class "Default")
      (node (ref "R14") (pin "2") (pinfunction "2_2") (pintype "passive"))
      (node (ref "U4") (pin "23") (pinfunction "CRS_23") (pintype "passive"))
    )
    (net (code "100") (name "Net-(U4-LED1{slash}AD1)") (class "Default")
      (node (ref "R17") (pin "2") (pinfunction "2_2") (pintype "passive"))
      (node (ref "U4") (pin "10") (pinfunction "LED1/AD1_10") (pintype "passive"))
    )
    (net (code "101") (name "Net-(U4-LED2{slash}AD2)") (class "Default")
      (node (ref "R19") (pin "2") (pinfunction "2_2") (pintype "passive"))
      (node (ref "U4") (pin "12") (pinfunction "LED2/AD2_12") (pintype "passive"))
    )
    (net (code "102") (name "Net-(U4-LED4{slash}AD4)") (class "Default")
      (node (ref "R21") (pin "2") (pinfunction "2_2") (pintype "passive"))
      (node (ref "U4") (pin "15") (pinfunction "LED4/AD4_15") (pintype "passive"))
    )
    (net (code "103") (name "Net-(U4-RTSET)") (class "Default")
      (node (ref "R13") (pin "1") (pinfunction "1_1") (pintype "passive"))
      (node (ref "U4") (pin "28") (pinfunction "RTSET_28") (pintype "passive"))
    )
    (net (code "104") (name "Net-(U4-X1)") (class "Default")
      (node (ref "C46") (pin "1") (pinfunction "1_1") (pintype "passive"))
      (node (ref "U4") (pin "46") (pinfunction "X1_46") (pintype "passive"))
      (node (ref "X3") (pin "1") (pinfunction "1_1") (pintype "passive"))
    )
    (net (code "105") (name "Net-(U4-X2)") (class "Default")
      (node (ref "C44") (pin "1") (pinfunction "1_1") (pintype "passive"))
      (node (ref "U4") (pin "47") (pinfunction "X2_47") (pintype "passive"))
      (node (ref "X3") (pin "2") (pinfunction "2_2") (pintype "passive"))
    )
    (net (code "106") (name "Net-(U6-CLOCK)") (class "Default")
      (node (ref "R18") (pin "1") (pinfunction "1_1") (pintype "passive"))
      (node (ref "U6") (pin "24") (pinfunction "CLOCK_24") (pintype "passive"))
    )
    (net (code "107") (name "Net-(U6-COMP)") (class "Default")
      (node (ref "C38") (pin "1") (pinfunction "1_1") (pintype "passive"))
      (node (ref "U6") (pin "35") (pinfunction "COMP_35") (pintype "passive"))
    )
    (net (code "108") (name "Net-(U6-RSET)") (class "Default")
      (node (ref "R12") (pin "1") (pinfunction "1_1") (pintype "passive"))
      (node (ref "U6") (pin "37") (pinfunction "RSET_37") (pintype "passive"))
    )
    (net (code "109") (name "Net-(U6-VREF)") (class "Default")
      (node (ref "C37") (pin "1") (pinfunction "1_1") (pintype "passive"))
      (node (ref "U6") (pin "36") (pinfunction "VREF_36") (pintype "passive"))
    )
    (net (code "110") (name "Net-(U6-~{PSAVE})") (class "Default")
      (node (ref "R11") (pin "1") (pinfunction "1_1") (pintype "passive"))
      (node (ref "U6") (pin "38") (pinfunction "~{PSAVE}_38") (pintype "passive"))
    )
    (net (code "111") (name "Net-(VGA1-HSYNC)") (class "Default")
      (node (ref "R26") (pin "2") (pinfunction "2_2") (pintype "passive"))
      (node (ref "VGA1") (pin "13") (pinfunction "HSYNC_13") (pintype "passive"))
    )
    (net (code "112") (name "Net-(VGA1-VSYNC)") (class "Default")
      (node (ref "R25") (pin "2") (pinfunction "2_2") (pintype "passive"))
      (node (ref "VGA1") (pin "14") (pinfunction "VSYNC_14") (pintype "passive"))
    )
    (net (code "113") (name "VCC3.3") (class "Default")
      (node (ref "C37") (pin "2") (pinfunction "2_2") (pintype "passive"))
      (node (ref "C38") (pin "2") (pinfunction "2_2") (pintype "passive"))
      (node (ref "C39") (pin "2") (pinfunction "2_2") (pintype "passive"))
      (node (ref "C41") (pin "2") (pinfunction "2_2") (pintype "passive"))
      (node (ref "C42") (pin "2") (pinfunction "2_2") (pintype "passive"))
      (node (ref "C43") (pin "2") (pinfunction "2_2") (pintype "passive"))
      (node (ref "C45") (pin "1") (pinfunction "1_1") (pintype "passive"))
      (node (ref "C49") (pin "2") (pinfunction "2_2") (pintype "passive"))
      (node (ref "C50") (pin "2") (pinfunction "2_2") (pintype "passive"))
      (node (ref "C51") (pin "2") (pinfunction "2_2") (pintype "passive"))
      (node (ref "C52") (pin "2") (pinfunction "2_2") (pintype "passive"))
      (node (ref "C53") (pin "2") (pinfunction "2_2") (pintype "passive"))
      (node (ref "C54") (pin "2") (pinfunction "2_2") (pintype "passive"))
      (node (ref "C55") (pin "2") (pinfunction "2_2") (pintype "passive"))
      (node (ref "C56") (pin "2") (pinfunction "2_2") (pintype "passive"))
      (node (ref "R10") (pin "2") (pinfunction "2_2") (pintype "passive"))
      (node (ref "R11") (pin "2") (pinfunction "2_2") (pintype "passive"))
      (node (ref "R15") (pin "1") (pinfunction "1_1") (pintype "passive"))
      (node (ref "R16") (pin "1") (pinfunction "1_1") (pintype "passive"))
      (node (ref "R17") (pin "1") (pinfunction "1_1") (pintype "passive"))
      (node (ref "R19") (pin "1") (pinfunction "1_1") (pintype "passive"))
      (node (ref "R20") (pin "1") (pinfunction "1_1") (pintype "passive"))
      (node (ref "R21") (pin "1") (pinfunction "1_1") (pintype "passive"))
      (node (ref "R22") (pin "2") (pinfunction "2_2") (pintype "passive"))
      (node (ref "R23") (pin "2") (pinfunction "2_2") (pintype "passive"))
      (node (ref "R9") (pin "2") (pinfunction "2_2") (pintype "passive"))
      (node (ref "U4") (pin "14") (pinfunction "DVDD33_14") (pintype "passive"))
      (node (ref "U4") (pin "36") (pinfunction "AVDD33_36") (pintype "passive"))
      (node (ref "U4") (pin "37") (pinfunction "ANE_37") (pintype "passive"))
      (node (ref "U4") (pin "38") (pinfunction "DUPLEX_38") (pintype "passive"))
      (node (ref "U4") (pin "39") (pinfunction "SPEED_39") (pintype "passive"))
      (node (ref "U4") (pin "44") (pinfunction "MII/SNIB_44") (pintype "passive"))
      (node (ref "U4") (pin "48") (pinfunction "DVDD33_48") (pintype "passive"))
      (node (ref "U5") (pin "1") (pinfunction "VDD0_1") (pintype "power_in"))
      (node (ref "U5") (pin "14") (pinfunction "VDD1_14") (pintype "power_in"))
      (node (ref "U5") (pin "27") (pinfunction "VDD2_27") (pintype "power_in"))
      (node (ref "U5") (pin "3") (pinfunction "VDDQ0_3") (pintype "power_in"))
      (node (ref "U5") (pin "43") (pinfunction "VDDQ2_43") (pintype "power_in"))
      (node (ref "U5") (pin "49") (pinfunction "VDDQ3_49") (pintype "power_in"))
      (node (ref "U5") (pin "9") (pinfunction "VDDQ1_9") (pintype "power_in"))
      (node (ref "U6") (pin "13") (pinfunction "VAA_13") (pintype "passive"))
      (node (ref "U6") (pin "29") (pinfunction "VAA_29") (pintype "passive"))
      (node (ref "U6") (pin "30") (pinfunction "VAA_30") (pintype "passive"))
    )
    (net (code "114") (name "unconnected-(ETHNET1-NC-Pad7)") (class "Default")
      (node (ref "ETHNET1") (pin "7") (pinfunction "NC_7") (pintype "passive"))
    )
    (net (code "115") (name "unconnected-(U4-NC-Pad27)") (class "Default")
      (node (ref "U4") (pin "27") (pinfunction "NC_27") (pintype "passive+no_connect"))
    )
    (net (code "116") (name "unconnected-(U4-RXER{slash}FXEN-Pad24)") (class "Default")
      (node (ref "U4") (pin "24") (pinfunction "RXER/FXEN_24") (pintype "passive+no_connect"))
    )
    (net (code "117") (name "unconnected-(VGA1-ID0-Pad11)") (class "Default")
      (node (ref "VGA1") (pin "11") (pinfunction "ID0_11") (pintype "passive+no_connect"))
    )
    (net (code "118") (name "unconnected-(VGA1-ID1-Pad12)") (class "Default")
      (node (ref "VGA1") (pin "12") (pinfunction "ID1_12") (pintype "passive+no_connect"))
    )
    (net (code "119") (name "unconnected-(VGA1-ID2-Pad4)") (class "Default")
      (node (ref "VGA1") (pin "4") (pinfunction "ID2_4") (pintype "passive+no_connect"))
    )
    (net (code "120") (name "unconnected-(VGA1-ID3-Pad15)") (class "Default")
      (node (ref "VGA1") (pin "15") (pinfunction "ID3_15") (pintype "passive+no_connect"))
    )
    (net (code "121") (name "unconnected-(VGA1-KEY-Pad9)") (class "Default")
      (node (ref "VGA1") (pin "9") (pinfunction "KEY_9") (pintype "passive+no_connect"))
    )
  )
)
